# BC118_Mate.net
KiCad netlist of a schematic drawn in EAGLE
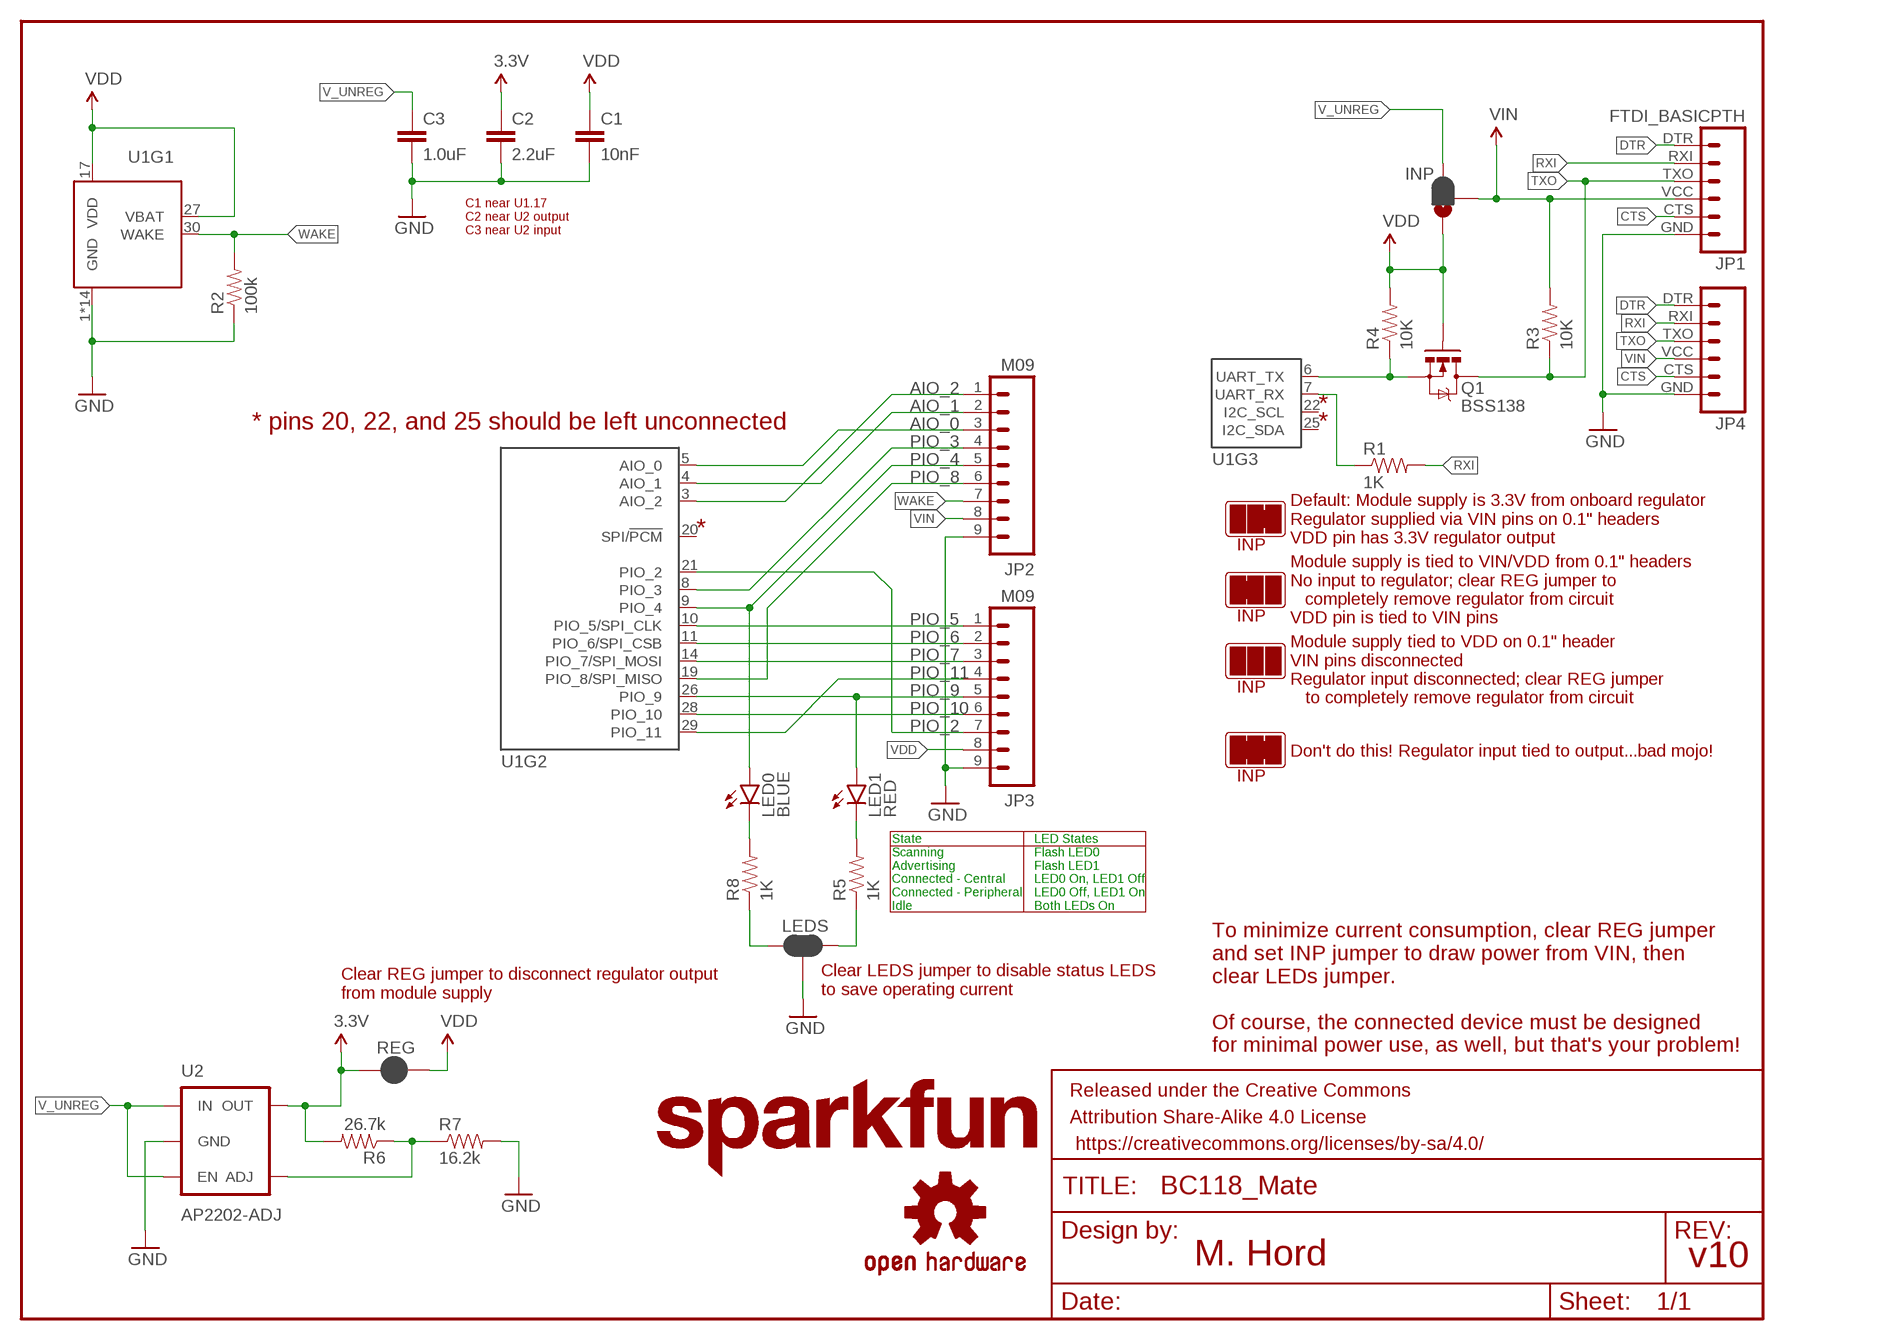
[diagram p0: schematic, sheet 1]

(export (version "E")
  (design (tool "Eeschema 10.0.6"))
  (components
    (comp (ref "C1")
      (value "10nF")
      (footprint "eagle-import:0603-CAP")
      (libsource (lib "eagle-import") (part "10NF/10000PF-50V-10%(0603)"))
    )
    (comp (ref "C2")
      (value "2.2uF")
      (footprint "eagle-import:0603-CAP")
      (libsource (lib "eagle-import") (part "2.2UF-10V-20%(0603)"))
    )
    (comp (ref "C3")
      (value "1.0uF")
      (footprint "eagle-import:0603-CAP")
      (libsource (lib "eagle-import") (part "1.0UF-16V-10%(0603)"))
    )
    (comp (ref "FRAME1")
      (value "FRAME-LETTER")
      (footprint "eagle-import:CREATIVE_COMMONS")
      (libsource (lib "eagle-import") (part "FRAME-LETTER"))
    )
    (comp (ref "INP")
      (value "JUMPER-PAD-3-2OF3_NC_BY_PASTE")
      (footprint "eagle-import:PAD-JUMPER-3-2OF3_NC_BY_PASTE_YES_SILK_FULL_BOX")
      (libsource (lib "eagle-import") (part "JUMPER-PAD-3-2OF3_NC_BY_PASTE"))
    )
    (comp (ref "JP1")
      (value "FTDI_BASICPTH")
      (footprint "eagle-import:FTDI_BASIC")
      (libsource (lib "eagle-import") (part "FTDI_BASICPTH"))
    )
    (comp (ref "JP2")
      (value "M09")
      (footprint "eagle-import:1X09")
      (libsource (lib "eagle-import") (part "M09"))
    )
    (comp (ref "JP3")
      (value "M09")
      (footprint "eagle-import:1X09")
      (libsource (lib "eagle-import") (part "M09"))
    )
    (comp (ref "JP4")
      (value "M06SIP")
      (footprint "eagle-import:1X06")
      (libsource (lib "eagle-import") (part "M06SIP"))
    )
    (comp (ref "LED0")
      (value "BLUE")
      (footprint "eagle-import:LED-0603")
      (libsource (lib "eagle-import") (part "LED-BLUE0603"))
    )
    (comp (ref "LED1")
      (value "RED")
      (footprint "eagle-import:LED-0603")
      (libsource (lib "eagle-import") (part "LED-RED0603"))
    )
    (comp (ref "LEDS")
      (value "JUMPER-PAD-3-NC_BY_PASTE")
      (footprint "eagle-import:PAD-JUMPER-3-NC_BY_PASTE_YES_SILK_FULL_BOX")
      (libsource (lib "eagle-import") (part "JUMPER-PAD-3-NC_BY_PASTE"))
    )
    (comp (ref "LOGO1")
      (value "SFE_LOGO_NAME.1_INCH")
      (footprint "eagle-import:SFE_LOGO_NAME_.1")
      (libsource (lib "eagle-import") (part "SFE_LOGO_NAME.1_INCH"))
    )
    (comp (ref "LOGO2")
      (value "OSHW-LOGOS")
      (footprint "eagle-import:OSHW-LOGO-S")
      (libsource (lib "eagle-import") (part "OSHW-LOGOS"))
    )
    (comp (ref "LOGO3")
      (value "SFE_LOGO_NAME.1_INCH")
      (footprint "eagle-import:SFE_LOGO_NAME_.1")
      (libsource (lib "eagle-import") (part "SFE_LOGO_NAME.1_INCH"))
    )
    (comp (ref "LOGO4")
      (value "OSHW-LOGOS")
      (footprint "eagle-import:OSHW-LOGO-S")
      (libsource (lib "eagle-import") (part "OSHW-LOGOS"))
    )
    (comp (ref "Q1")
      (value "BSS138")
      (footprint "eagle-import:SOT23")
      (libsource (lib "eagle-import") (part "MOSFET-NCHANNELBSS138"))
    )
    (comp (ref "R1")
      (value "1K")
      (footprint "eagle-import:0603-RES")
      (libsource (lib "eagle-import") (part "1KOHM1/10W1%(0603)"))
    )
    (comp (ref "R2")
      (value "100k")
      (footprint "eagle-import:0603-RES")
      (libsource (lib "eagle-import") (part "100KOHM1/10W1%(0603)"))
    )
    (comp (ref "R3")
      (value "10K")
      (footprint "eagle-import:0603-RES")
      (libsource (lib "eagle-import") (part "10KOHM1/10W1%(0603)0603"))
    )
    (comp (ref "R4")
      (value "10K")
      (footprint "eagle-import:0603-RES")
      (libsource (lib "eagle-import") (part "10KOHM1/10W1%(0603)0603"))
    )
    (comp (ref "R5")
      (value "1K")
      (footprint "eagle-import:0603-RES")
      (libsource (lib "eagle-import") (part "1KOHM1/10W1%(0603)"))
    )
    (comp (ref "R6")
      (value "26.7k")
      (footprint "eagle-import:0603-RES")
      (libsource (lib "eagle-import") (part "26.7KOHM1/10W1%(0603)"))
    )
    (comp (ref "R7")
      (value "16.2k")
      (footprint "eagle-import:0603-RES")
      (libsource (lib "eagle-import") (part "16.2KOHM1/10W1%(0603)"))
    )
    (comp (ref "R8")
      (value "1K")
      (footprint "eagle-import:0603-RES")
      (libsource (lib "eagle-import") (part "1KOHM1/10W1%(0603)"))
    )
    (comp (ref "REG")
      (value "JUMPER-PAD-2-NC_BY_PASTE")
      (footprint "eagle-import:PAD-JUMPER-2-NC_BY_PASTE_YES_SILK")
      (libsource (lib "eagle-import") (part "JUMPER-PAD-2-NC_BY_PASTE"))
    )
    (comp (ref "U1")
      (value "BC118")
      (footprint "eagle-import:BC118")
      (libsource (lib "eagle-import") (part "BC118"))
    )
    (comp (ref "U2")
      (value "AP2202-ADJ")
      (footprint "eagle-import:SOT23-5")
      (libsource (lib "eagle-import") (part "AP2202-ADJ"))
    )
  )
  (nets
    (net (code "1") (name "/AIO_0") (class "Default")
      (node (ref "JP2") (pin "3") (pinfunction "3_3") (pintype "passive"))
      (node (ref "U1") (pin "5") (pinfunction "AIO_0_5") (pintype "bidirectional"))
    )
    (net (code "2") (name "/AIO_1") (class "Default")
      (node (ref "JP2") (pin "2") (pinfunction "2_2") (pintype "passive"))
      (node (ref "U1") (pin "4") (pinfunction "AIO_1_4") (pintype "bidirectional"))
    )
    (net (code "3") (name "/AIO_2") (class "Default")
      (node (ref "JP2") (pin "1") (pinfunction "1_1") (pintype "passive"))
      (node (ref "U1") (pin "3") (pinfunction "AIO_2_3") (pintype "bidirectional"))
    )
    (net (code "4") (name "/PIO_2") (class "Default")
      (node (ref "JP3") (pin "7") (pinfunction "7_7") (pintype "passive"))
      (node (ref "U1") (pin "21") (pinfunction "PIO_2_21") (pintype "bidirectional"))
    )
    (net (code "5") (name "/PIO_3") (class "Default")
      (node (ref "JP2") (pin "4") (pinfunction "4_4") (pintype "passive"))
      (node (ref "U1") (pin "8") (pinfunction "PIO_3_8") (pintype "bidirectional"))
    )
    (net (code "6") (name "/PIO_4") (class "Default")
      (node (ref "JP2") (pin "5") (pinfunction "5_5") (pintype "passive"))
      (node (ref "LED0") (pin "A") (pinfunction "A_A") (pintype "passive"))
      (node (ref "U1") (pin "9") (pinfunction "PIO_4_9") (pintype "bidirectional"))
    )
    (net (code "7") (name "/PIO_5") (class "Default")
      (node (ref "JP3") (pin "1") (pinfunction "1_1") (pintype "passive"))
      (node (ref "U1") (pin "10") (pinfunction "PIO_5/SPI_CLK_10") (pintype "bidirectional"))
    )
    (net (code "8") (name "/PIO_6") (class "Default")
      (node (ref "JP3") (pin "2") (pinfunction "2_2") (pintype "passive"))
      (node (ref "U1") (pin "11") (pinfunction "PIO_6/SPI_CSB_11") (pintype "bidirectional"))
    )
    (net (code "9") (name "/PIO_7") (class "Default")
      (node (ref "JP3") (pin "3") (pinfunction "3_3") (pintype "passive"))
      (node (ref "U1") (pin "14") (pinfunction "PIO_7/SPI_MOSI_14") (pintype "bidirectional"))
    )
    (net (code "10") (name "/PIO_8") (class "Default")
      (node (ref "JP2") (pin "6") (pinfunction "6_6") (pintype "passive"))
      (node (ref "U1") (pin "19") (pinfunction "PIO_8/SPI_MISO_19") (pintype "bidirectional"))
    )
    (net (code "11") (name "/PIO_9") (class "Default")
      (node (ref "JP3") (pin "5") (pinfunction "5_5") (pintype "passive"))
      (node (ref "LED1") (pin "A") (pinfunction "A_A") (pintype "passive"))
      (node (ref "U1") (pin "26") (pinfunction "PIO_9_26") (pintype "bidirectional"))
    )
    (net (code "12") (name "/PIO_10") (class "Default")
      (node (ref "JP3") (pin "6") (pinfunction "6_6") (pintype "passive"))
      (node (ref "U1") (pin "28") (pinfunction "PIO_10_28") (pintype "bidirectional"))
    )
    (net (code "13") (name "/PIO_11") (class "Default")
      (node (ref "JP3") (pin "4") (pinfunction "4_4") (pintype "passive"))
      (node (ref "U1") (pin "29") (pinfunction "PIO_11_29") (pintype "bidirectional"))
    )
    (net (code "14") (name "3.3V") (class "Default")
      (node (ref "C2") (pin "1") (pinfunction "1_1") (pintype "passive"))
      (node (ref "R6") (pin "2") (pinfunction "2_2") (pintype "passive"))
      (node (ref "REG") (pin "1") (pinfunction "1_1") (pintype "passive"))
      (node (ref "U2") (pin "5") (pinfunction "OUT_5") (pintype "passive"))
    )
    (net (code "15") (name "CTS") (class "Default")
      (node (ref "JP1") (pin "CTS") (pinfunction "5_CTS") (pintype "passive"))
      (node (ref "JP4") (pin "CTS") (pinfunction "5_CTS") (pintype "passive"))
    )
    (net (code "16") (name "DTR") (class "Default")
      (node (ref "JP1") (pin "DTR") (pinfunction "1_DTR") (pintype "passive"))
      (node (ref "JP4") (pin "DTR") (pinfunction "1_DTR") (pintype "passive"))
    )
    (net (code "17") (name "GND") (class "Default")
      (node (ref "C1") (pin "2") (pinfunction "2_2") (pintype "passive"))
      (node (ref "C2") (pin "2") (pinfunction "2_2") (pintype "passive"))
      (node (ref "C3") (pin "2") (pinfunction "2_2") (pintype "passive"))
      (node (ref "JP1") (pin "GND") (pinfunction "6_GND") (pintype "passive"))
      (node (ref "JP2") (pin "9") (pinfunction "9_9") (pintype "passive"))
      (node (ref "JP3") (pin "9") (pinfunction "9_9") (pintype "passive"))
      (node (ref "JP4") (pin "GND") (pinfunction "6_GND") (pintype "passive"))
      (node (ref "LEDS") (pin "2") (pinfunction "2_2") (pintype "passive"))
      (node (ref "R2") (pin "1") (pinfunction "1_1") (pintype "passive"))
      (node (ref "R7") (pin "2") (pinfunction "2_2") (pintype "passive"))
      (node (ref "U1") (pin "1") (pinfunction "GND_1") (pintype "bidirectional"))
      (node (ref "U1") (pin "12") (pinfunction "GND_12") (pintype "bidirectional"))
      (node (ref "U1") (pin "13") (pinfunction "GND_13") (pintype "bidirectional"))
      (node (ref "U1") (pin "15") (pinfunction "GND_15") (pintype "bidirectional"))
      (node (ref "U1") (pin "16") (pinfunction "GND_16") (pintype "bidirectional"))
      (node (ref "U1") (pin "18") (pinfunction "GND_18") (pintype "bidirectional"))
      (node (ref "U1") (pin "2") (pinfunction "GND_2") (pintype "bidirectional"))
      (node (ref "U1") (pin "23") (pinfunction "GND_23") (pintype "bidirectional"))
      (node (ref "U1") (pin "24") (pinfunction "GND_24") (pintype "bidirectional"))
      (node (ref "U1") (pin "31") (pinfunction "GND_31") (pintype "bidirectional"))
      (node (ref "U1") (pin "32") (pinfunction "GND_32") (pintype "bidirectional"))
      (node (ref "U1") (pin "33") (pinfunction "GND_33") (pintype "bidirectional"))
      (node (ref "U1") (pin "34") (pinfunction "GND_34") (pintype "bidirectional"))
      (node (ref "U1") (pin "35") (pinfunction "GND_35") (pintype "bidirectional"))
      (node (ref "U2") (pin "2") (pinfunction "GND_2") (pintype "input"))
    )
    (net (code "18") (name "Net-(LED0-PadC)") (class "Default")
      (node (ref "LED0") (pin "C") (pinfunction "C_C") (pintype "passive"))
      (node (ref "R8") (pin "2") (pinfunction "2_2") (pintype "passive"))
    )
    (net (code "19") (name "Net-(LED1-PadC)") (class "Default")
      (node (ref "LED1") (pin "C") (pinfunction "C_C") (pintype "passive"))
      (node (ref "R5") (pin "2") (pinfunction "2_2") (pintype "passive"))
    )
    (net (code "20") (name "Net-(LEDS-Pad1)") (class "Default")
      (node (ref "LEDS") (pin "1") (pinfunction "1_1") (pintype "passive"))
      (node (ref "R8") (pin "1") (pinfunction "1_1") (pintype "passive"))
    )
    (net (code "21") (name "Net-(LEDS-Pad3)") (class "Default")
      (node (ref "LEDS") (pin "3") (pinfunction "3_3") (pintype "passive"))
      (node (ref "R5") (pin "1") (pinfunction "1_1") (pintype "passive"))
    )
    (net (code "22") (name "Net-(Q1-S)") (class "Default")
      (node (ref "Q1") (pin "2") (pinfunction "S_2") (pintype "passive"))
      (node (ref "R4") (pin "1") (pinfunction "1_1") (pintype "passive"))
      (node (ref "U1") (pin "6") (pinfunction "UART_TX_6") (pintype "bidirectional"))
    )
    (net (code "23") (name "Net-(U1C-UART_RX)") (class "Default")
      (node (ref "R1") (pin "1") (pinfunction "1_1") (pintype "passive"))
      (node (ref "U1") (pin "7") (pinfunction "UART_RX_7") (pintype "bidirectional"))
    )
    (net (code "24") (name "Net-(U2-ADJ)") (class "Default")
      (node (ref "R6") (pin "1") (pinfunction "1_1") (pintype "passive"))
      (node (ref "R7") (pin "1") (pinfunction "1_1") (pintype "passive"))
      (node (ref "U2") (pin "4") (pinfunction "ADJ_4") (pintype "input"))
    )
    (net (code "25") (name "RXI") (class "Default")
      (node (ref "JP1") (pin "RXI") (pinfunction "2_RXI") (pintype "passive"))
      (node (ref "JP4") (pin "RXI") (pinfunction "2_RXI") (pintype "passive"))
      (node (ref "R1") (pin "2") (pinfunction "2_2") (pintype "passive"))
    )
    (net (code "26") (name "TXO") (class "Default")
      (node (ref "JP1") (pin "TXO") (pinfunction "3_TXO") (pintype "passive"))
      (node (ref "JP4") (pin "TXO") (pinfunction "3_TXO") (pintype "passive"))
      (node (ref "Q1") (pin "3") (pinfunction "D_3") (pintype "passive"))
      (node (ref "R3") (pin "1") (pinfunction "1_1") (pintype "passive"))
    )
    (net (code "27") (name "VDD") (class "Default")
      (node (ref "C1") (pin "1") (pinfunction "1_1") (pintype "passive"))
      (node (ref "INP") (pin "1") (pinfunction "1_1") (pintype "passive"))
      (node (ref "JP3") (pin "8") (pinfunction "8_8") (pintype "passive"))
      (node (ref "Q1") (pin "1") (pinfunction "G_1") (pintype "passive"))
      (node (ref "R4") (pin "2") (pinfunction "2_2") (pintype "passive"))
      (node (ref "REG") (pin "2") (pinfunction "2_2") (pintype "passive"))
      (node (ref "U1") (pin "17") (pinfunction "VDD_17") (pintype "bidirectional"))
      (node (ref "U1") (pin "27") (pinfunction "VBAT_27") (pintype "bidirectional"))
    )
    (net (code "28") (name "VIN") (class "Default")
      (node (ref "INP") (pin "2") (pinfunction "2_2") (pintype "passive"))
      (node (ref "JP1") (pin "VCC") (pinfunction "4_VCC") (pintype "passive"))
      (node (ref "JP2") (pin "8") (pinfunction "8_8") (pintype "passive"))
      (node (ref "JP4") (pin "VCC") (pinfunction "4_VCC") (pintype "passive"))
      (node (ref "R3") (pin "2") (pinfunction "2_2") (pintype "passive"))
    )
    (net (code "29") (name "V_UNREG") (class "Default")
      (node (ref "C3") (pin "1") (pinfunction "1_1") (pintype "passive"))
      (node (ref "INP") (pin "3") (pinfunction "3_3") (pintype "passive"))
      (node (ref "U2") (pin "1") (pinfunction "IN_1") (pintype "input"))
      (node (ref "U2") (pin "3") (pinfunction "EN_3") (pintype "input"))
    )
    (net (code "30") (name "WAKE") (class "Default")
      (node (ref "JP2") (pin "7") (pinfunction "7_7") (pintype "passive"))
      (node (ref "R2") (pin "2") (pinfunction "2_2") (pintype "passive"))
      (node (ref "U1") (pin "30") (pinfunction "WAKE_30") (pintype "bidirectional"))
    )
    (net (code "31") (name "unconnected-(U1B-SPI{slash}~{PCM}-Pad20)") (class "Default")
      (node (ref "U1") (pin "20") (pinfunction "SPI/~{PCM}_20") (pintype "bidirectional"))
    )
    (net (code "32") (name "unconnected-(U1C-I2C_SCL-Pad22)") (class "Default")
      (node (ref "U1") (pin "22") (pinfunction "I2C_SCL_22") (pintype "bidirectional"))
    )
    (net (code "33") (name "unconnected-(U1C-I2C_SDA-Pad25)") (class "Default")
      (node (ref "U1") (pin "25") (pinfunction "I2C_SDA_25") (pintype "bidirectional"))
    )
  )
)
